# SCH_HUB-USB_2025-02-13.net
KiCad netlist of a schematic drawn in EasyEDA
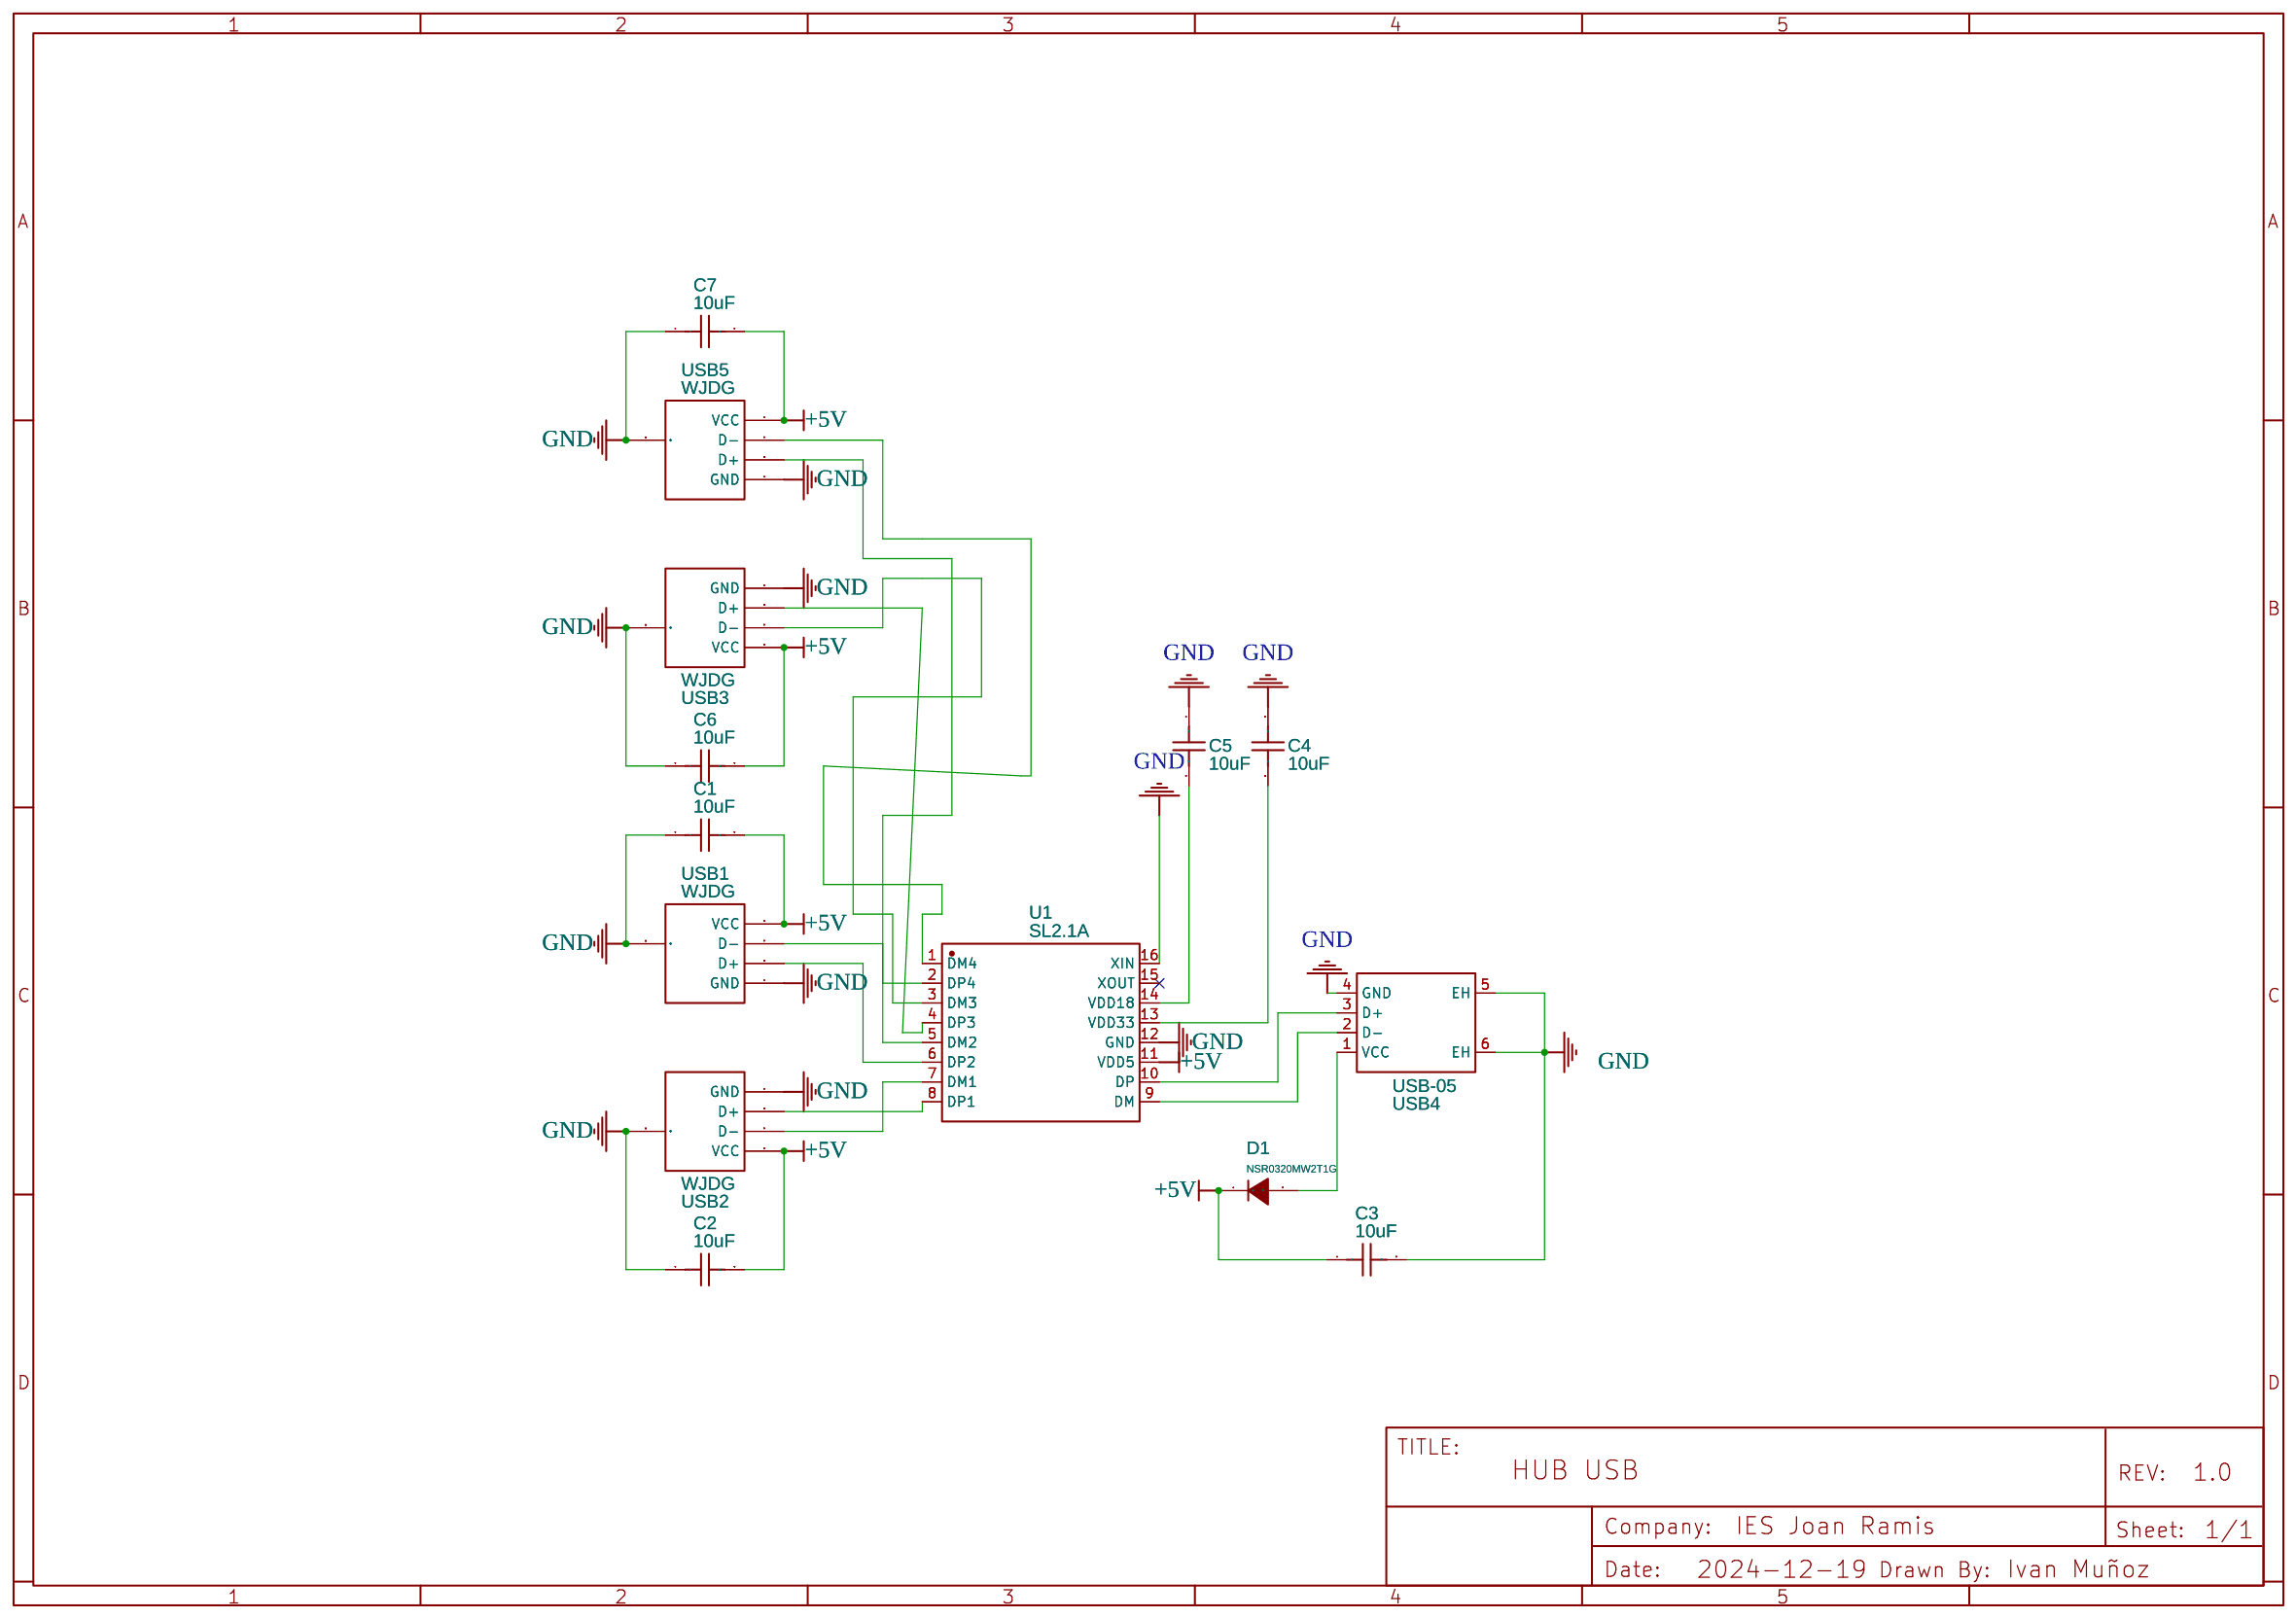
[diagram p0: schematic sheet]

(export (version "E")
  (design (tool "Eeschema 10.0.6"))
  (components
    (comp (ref "C1")
      (value "10uF")
      (fields
        (field (name "Manufacturer Part") "CL10A106KP8NNNC")
        (field (name "Manufacturer") "SAMSUNG(三星)")
      )
      (libsource (lib "") (part "CL10A106KP8NNNC"))
    )
    (comp (ref "C2")
      (value "10uF")
      (fields
        (field (name "Manufacturer Part") "CL10A106KP8NNNC")
        (field (name "Manufacturer") "SAMSUNG(三星)")
      )
      (libsource (lib "") (part "CL10A106KP8NNNC"))
    )
    (comp (ref "C3")
      (value "10uF")
      (fields
        (field (name "Manufacturer Part") "CL10A106KP8NNNC")
        (field (name "Manufacturer") "SAMSUNG(三星)")
      )
      (libsource (lib "") (part "CL10A106KP8NNNC"))
    )
    (comp (ref "C4")
      (value "10uF")
      (fields
        (field (name "Manufacturer Part") "CL10A106KP8NNNC")
        (field (name "Manufacturer") "SAMSUNG(三星)")
      )
      (libsource (lib "") (part "CL10A106KP8NNNC_1"))
    )
    (comp (ref "C5")
      (value "10uF")
      (fields
        (field (name "Manufacturer Part") "CL10A106KP8NNNC")
        (field (name "Manufacturer") "SAMSUNG(三星)")
      )
      (libsource (lib "") (part "CL10A106KP8NNNC_1"))
    )
    (comp (ref "C6")
      (value "10uF")
      (fields
        (field (name "Manufacturer Part") "CL10A106KP8NNNC")
        (field (name "Manufacturer") "SAMSUNG(三星)")
      )
      (libsource (lib "") (part "CL10A106KP8NNNC"))
    )
    (comp (ref "C7")
      (value "10uF")
      (fields
        (field (name "Manufacturer Part") "CL10A106KP8NNNC")
        (field (name "Manufacturer") "SAMSUNG(三星)")
      )
      (libsource (lib "") (part "CL10A106KP8NNNC"))
    )
    (comp (ref "D1")
      (value "NSR0320MW2T1G")
      (fields (field (name "Manufacturer") "onsemi(安森美)"))
      (libsource (lib "") (part "NSR0320MW2T1G"))
    )
    (comp (ref "U1")
      (value "SL2.1A")
      (fields (field (name "Manufacturer") "CoreChips(和芯润德)"))
      (libsource (lib "") (part "SL2.1A"))
    )
    (comp (ref "USB1")
      (value "WJDG")
      (fields (field (name "Manufacturer Part") "AF 90° WJDG") (field (name "Manufacturer") "SHOU HAN(首韩)"))
      (libsource (lib "") (part "AF 90° WJDG"))
    )
    (comp (ref "USB2")
      (value "WJDG")
      (fields (field (name "Manufacturer Part") "AF 90° WJDG") (field (name "Manufacturer") "SHOU HAN(首韩)"))
      (libsource (lib "") (part "AF 90° WJDG_1"))
    )
    (comp (ref "USB3")
      (value "WJDG")
      (fields (field (name "Manufacturer Part") "AF 90° WJDG") (field (name "Manufacturer") "SHOU HAN(首韩)"))
      (libsource (lib "") (part "AF 90° WJDG_1"))
    )
    (comp (ref "USB4")
      (value "USB-05")
      (fields (field (name "Manufacturer") "SOFNG(硕方)"))
      (libsource (lib "") (part "USB-05"))
    )
    (comp (ref "USB5")
      (value "WJDG")
      (fields (field (name "Manufacturer Part") "AF 90° WJDG") (field (name "Manufacturer") "SHOU HAN(首韩)"))
      (libsource (lib "") (part "AF 90° WJDG"))
    )
  )
  (nets
    (net (code "1") (name "+5V") (class "Default")
      (node (ref "C1") (pin "2") (pinfunction "2_2") (pintype "unspecified"))
      (node (ref "C2") (pin "2") (pinfunction "2_2") (pintype "unspecified"))
      (node (ref "C3") (pin "1") (pinfunction "1_1") (pintype "unspecified"))
      (node (ref "C6") (pin "2") (pinfunction "2_2") (pintype "unspecified"))
      (node (ref "C7") (pin "2") (pinfunction "2_2") (pintype "unspecified"))
      (node (ref "D1") (pin "1") (pinfunction "C_1") (pintype "unspecified"))
      (node (ref "U1") (pin "11") (pinfunction "VDD5_11") (pintype "unspecified"))
      (node (ref "USB1") (pin "1") (pinfunction "VCC_1") (pintype "input"))
      (node (ref "USB2") (pin "1") (pinfunction "VCC_1") (pintype "input"))
      (node (ref "USB3") (pin "1") (pinfunction "VCC_1") (pintype "input"))
      (node (ref "USB5") (pin "1") (pinfunction "VCC_1") (pintype "input"))
    )
    (net (code "2") (name "GND") (class "Default")
      (node (ref "C1") (pin "1") (pinfunction "1_1") (pintype "unspecified"))
      (node (ref "C2") (pin "1") (pinfunction "1_1") (pintype "unspecified"))
      (node (ref "C3") (pin "2") (pinfunction "2_2") (pintype "unspecified"))
      (node (ref "C4") (pin "1") (pinfunction "1_1") (pintype "unspecified"))
      (node (ref "C5") (pin "1") (pinfunction "1_1") (pintype "unspecified"))
      (node (ref "C6") (pin "1") (pinfunction "1_1") (pintype "unspecified"))
      (node (ref "C7") (pin "1") (pinfunction "1_1") (pintype "unspecified"))
      (node (ref "U1") (pin "12") (pinfunction "GND_12") (pintype "unspecified"))
      (node (ref "U1") (pin "16") (pinfunction "XIN_16") (pintype "unspecified"))
      (node (ref "USB1") (pin "4") (pinfunction "GND_4") (pintype "input"))
      (node (ref "USB1") (pin "5") (pinfunction "SHLD_5") (pintype "unspecified"))
      (node (ref "USB2") (pin "4") (pinfunction "GND_4") (pintype "input"))
      (node (ref "USB2") (pin "5") (pinfunction "SHLD_5") (pintype "unspecified"))
      (node (ref "USB3") (pin "4") (pinfunction "GND_4") (pintype "input"))
      (node (ref "USB3") (pin "5") (pinfunction "SHLD_5") (pintype "unspecified"))
      (node (ref "USB4") (pin "4") (pinfunction "GND_4") (pintype "input"))
      (node (ref "USB4") (pin "5") (pinfunction "EH_5") (pintype "unspecified"))
      (node (ref "USB4") (pin "6") (pinfunction "EH_6") (pintype "unspecified"))
      (node (ref "USB5") (pin "4") (pinfunction "GND_4") (pintype "input"))
      (node (ref "USB5") (pin "5") (pinfunction "SHLD_5") (pintype "unspecified"))
    )
    (net (code "3") (name "Net-(D1-A)") (class "Default")
      (node (ref "D1") (pin "2") (pinfunction "A_2") (pintype "unspecified"))
      (node (ref "USB4") (pin "1") (pinfunction "VCC_1") (pintype "input"))
    )
    (net (code "4") (name "Net-(U1-DM)") (class "Default")
      (node (ref "U1") (pin "9") (pinfunction "DM_9") (pintype "unspecified"))
      (node (ref "USB4") (pin "2") (pinfunction "D-_2") (pintype "input"))
    )
    (net (code "5") (name "Net-(U1-DM1)") (class "Default")
      (node (ref "U1") (pin "7") (pinfunction "DM1_7") (pintype "unspecified"))
      (node (ref "USB2") (pin "2") (pinfunction "D-_2") (pintype "input"))
    )
    (net (code "6") (name "Net-(U1-DM2)") (class "Default")
      (node (ref "U1") (pin "5") (pinfunction "DM2_5") (pintype "unspecified"))
      (node (ref "USB1") (pin "2") (pinfunction "D-_2") (pintype "input"))
    )
    (net (code "7") (name "Net-(U1-DM3)") (class "Default")
      (node (ref "U1") (pin "3") (pinfunction "DM3_3") (pintype "unspecified"))
      (node (ref "USB3") (pin "2") (pinfunction "D-_2") (pintype "input"))
    )
    (net (code "8") (name "Net-(U1-DM4)") (class "Default")
      (node (ref "U1") (pin "1") (pinfunction "DM4_1") (pintype "unspecified"))
      (node (ref "USB5") (pin "2") (pinfunction "D-_2") (pintype "input"))
    )
    (net (code "9") (name "Net-(U1-DP)") (class "Default")
      (node (ref "U1") (pin "10") (pinfunction "DP_10") (pintype "unspecified"))
      (node (ref "USB4") (pin "3") (pinfunction "D+_3") (pintype "input"))
    )
    (net (code "10") (name "Net-(U1-DP1)") (class "Default")
      (node (ref "U1") (pin "8") (pinfunction "DP1_8") (pintype "unspecified"))
      (node (ref "USB2") (pin "3") (pinfunction "D+_3") (pintype "input"))
    )
    (net (code "11") (name "Net-(U1-DP2)") (class "Default")
      (node (ref "U1") (pin "6") (pinfunction "DP2_6") (pintype "unspecified"))
      (node (ref "USB1") (pin "3") (pinfunction "D+_3") (pintype "input"))
    )
    (net (code "12") (name "Net-(U1-DP3)") (class "Default")
      (node (ref "U1") (pin "4") (pinfunction "DP3_4") (pintype "unspecified"))
      (node (ref "USB3") (pin "3") (pinfunction "D+_3") (pintype "input"))
    )
    (net (code "13") (name "Net-(U1-DP4)") (class "Default")
      (node (ref "U1") (pin "2") (pinfunction "DP4_2") (pintype "unspecified"))
      (node (ref "USB5") (pin "3") (pinfunction "D+_3") (pintype "input"))
    )
    (net (code "14") (name "Net-(U1-VDD18)") (class "Default")
      (node (ref "C5") (pin "2") (pinfunction "2_2") (pintype "unspecified"))
      (node (ref "U1") (pin "14") (pinfunction "VDD18_14") (pintype "unspecified"))
    )
    (net (code "15") (name "Net-(U1-VDD33)") (class "Default")
      (node (ref "C4") (pin "2") (pinfunction "2_2") (pintype "unspecified"))
      (node (ref "U1") (pin "13") (pinfunction "VDD33_13") (pintype "unspecified"))
    )
    (net (code "16") (name "unconnected-(U1-XOUT-Pad15)") (class "Default")
      (node (ref "U1") (pin "15") (pinfunction "XOUT_15") (pintype "unspecified+no_connect"))
    )
  )
)
